# artisansTomePcb.net
KiCad netlist of a schematic drawn in EasyEDA Pro
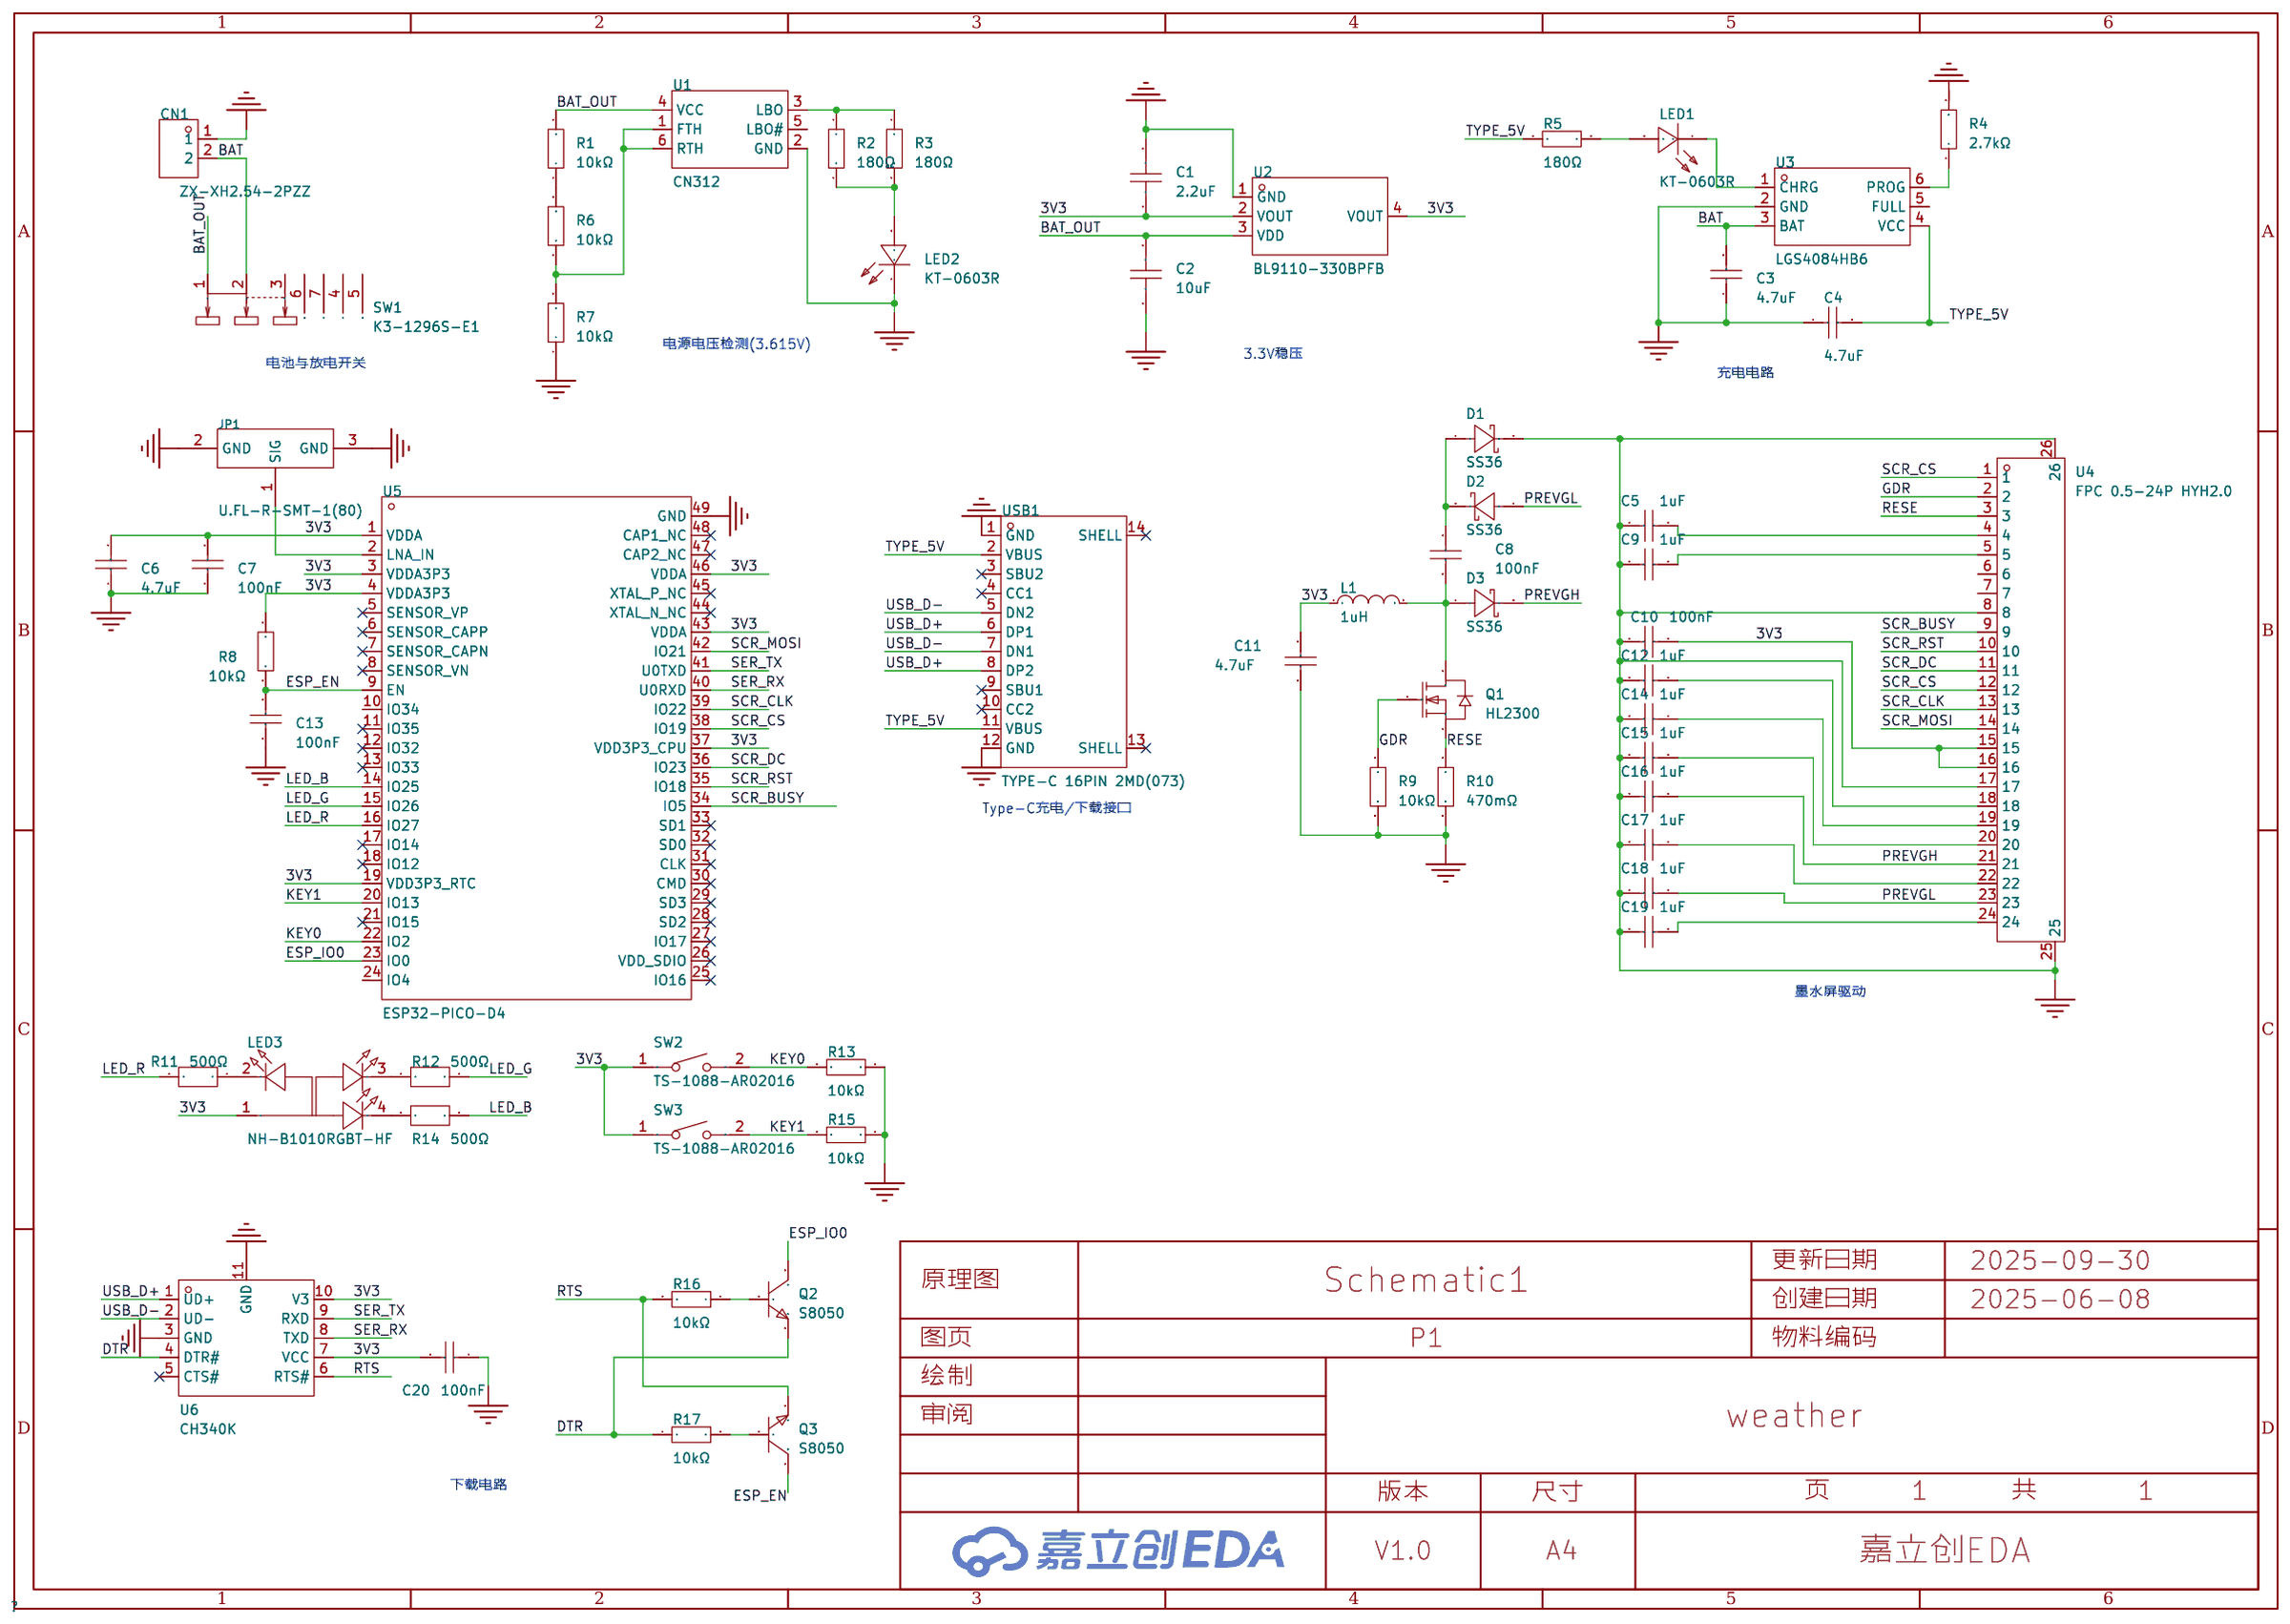
[diagram p0: schematic sheet]

(export (version "E")
  (design (tool "Eeschema 10.0.6"))
  (components
    (comp (ref "C1")
      (value "2.2uF")
      (footprint "easyedapro:C0402")
      (description "容值:2.2uF;精度:±10%;额定电压:16V;材质(温度系数):X5R;")
      (fields
        (field (name "Manufacturer Part") "HGC0402R5225K160NTEJ")
        (field (name "Manufacturer") "Chinocera(华瓷)")
      )
      (libsource (lib "easyedapro") (part "HGC0402R5225K160NTEJ"))
    )
    (comp (ref "C2")
      (value "10uF")
      (footprint "easyedapro:C0402")
      (description "容值:10uF;精度:±20%;额定电压:10V;材质(温度系数):X5R;")
      (fields
        (field (name "Manufacturer Part") "CGA0402X5R106M100GT")
        (field (name "Manufacturer") "HRE(芯声)")
      )
      (libsource (lib "easyedapro") (part "CGA0402X5R106M100GT"))
    )
    (comp (ref "C3")
      (value "4.7uF")
      (footprint "easyedapro:C0402")
      (description "容值:10uF;精度:±20%;额定电压:6.3V;材质(温度系数):X5R;")
      (fields
        (field (name "Manufacturer Part") "CL05A475MP5NRNC")
        (field (name "Manufacturer") "SAMSUNG(三星)")
      )
      (libsource (lib "easyedapro") (part "CL05A106MQ5NUNC"))
    )
    (comp (ref "C4")
      (value "4.7uF")
      (footprint "easyedapro:C0402")
      (description "容值:10uF;精度:±20%;额定电压:6.3V;材质(温度系数):X5R;")
      (fields
        (field (name "Manufacturer Part") "CL05A475MP5NRNC")
        (field (name "Manufacturer") "SAMSUNG(三星)")
      )
      (libsource (lib "easyedapro") (part "CL05A106MQ5NUNC"))
    )
    (comp (ref "C5")
      (value "1uF")
      (footprint "easyedapro:C0402")
      (description "容值:10uF;精度:±20%;额定电压:6.3V;材质(温度系数):X5R;")
      (fields
        (field (name "Manufacturer Part") "CL05A106MQ5NUNC")
        (field (name "Manufacturer") "SAMSUNG(三星)")
      )
      (libsource (lib "easyedapro") (part "CL05A106MQ5NUNC"))
    )
    (comp (ref "C6")
      (value "4.7uF")
      (footprint "easyedapro:C0402")
      (description "容值:10uF;精度:±20%;额定电压:6.3V;材质(温度系数):X5R;")
      (fields
        (field (name "Manufacturer Part") "CL05A475MP5NRNC")
        (field (name "Manufacturer") "SAMSUNG(三星)")
      )
      (libsource (lib "easyedapro") (part "CL05A106MQ5NUNC"))
    )
    (comp (ref "C7")
      (value "100nF")
      (footprint "easyedapro:C0402")
      (description "容值:100nF;精度:±10%;额定电压:16V;材质(温度系数):X7R;")
      (fields
        (field (name "Manufacturer Part") "CL05B104KO5NNNC")
        (field (name "Manufacturer") "SAMSUNG(三星)")
      )
      (libsource (lib "easyedapro") (part "CL05B104KO5NNNC"))
    )
    (comp (ref "C8")
      (value "100nF")
      (footprint "easyedapro:C0402")
      (description "容值:100nF;精度:±10%;额定电压:16V;温度系数:X7R;")
      (fields
        (field (name "Manufacturer Part") "CL05A106MQ5NUNC")
        (field (name "Manufacturer") "SAMSUNG(三星)")
      )
      (libsource (lib "easyedapro") (part "CL05A106MQ5NUNC"))
    )
    (comp (ref "C9")
      (value "1uF")
      (footprint "easyedapro:C0402")
      (description "容值:10uF;精度:±20%;额定电压:6.3V;材质(温度系数):X5R;")
      (fields
        (field (name "Manufacturer Part") "CL05A106MQ5NUNC")
        (field (name "Manufacturer") "SAMSUNG(三星)")
      )
      (libsource (lib "easyedapro") (part "CL05A106MQ5NUNC"))
    )
    (comp (ref "C10")
      (value "100nF")
      (footprint "easyedapro:C0402")
      (description "容值:100nF;精度:±10%;额定电压:16V;材质(温度系数):X7R;")
      (fields
        (field (name "Manufacturer Part") "CL05B104KO5NNNC")
        (field (name "Manufacturer") "SAMSUNG(三星)")
      )
      (libsource (lib "easyedapro") (part "CL05B104KO5NNNC"))
    )
    (comp (ref "C11")
      (value "4.7uF")
      (footprint "easyedapro:C0402")
      (description "容值:10uF;精度:±20%;额定电压:6.3V;材质(温度系数):X5R;")
      (fields
        (field (name "Manufacturer Part") "CL05A475MP5NRNC")
        (field (name "Manufacturer") "SAMSUNG(三星)")
      )
      (libsource (lib "easyedapro") (part "CL05A106MQ5NUNC"))
    )
    (comp (ref "C12")
      (value "1uF")
      (footprint "easyedapro:C0402")
      (description "容值:10uF;精度:±20%;额定电压:6.3V;材质(温度系数):X5R;")
      (fields
        (field (name "Manufacturer Part") "CL05A106MQ5NUNC")
        (field (name "Manufacturer") "SAMSUNG(三星)")
      )
      (libsource (lib "easyedapro") (part "CL05A106MQ5NUNC"))
    )
    (comp (ref "C13")
      (value "100nF")
      (footprint "easyedapro:C0402")
      (description "容值:100nF;精度:±10%;额定电压:16V;材质(温度系数):X7R;")
      (fields
        (field (name "Manufacturer Part") "CL05B104KO5NNNC")
        (field (name "Manufacturer") "SAMSUNG(三星)")
      )
      (libsource (lib "easyedapro") (part "CL05B104KO5NNNC"))
    )
    (comp (ref "C14")
      (value "1uF")
      (footprint "easyedapro:C0402")
      (description "容值:10uF;精度:±20%;额定电压:6.3V;材质(温度系数):X5R;")
      (fields
        (field (name "Manufacturer Part") "CL05A106MQ5NUNC")
        (field (name "Manufacturer") "SAMSUNG(三星)")
      )
      (libsource (lib "easyedapro") (part "CL05A106MQ5NUNC"))
    )
    (comp (ref "C15")
      (value "1uF")
      (footprint "easyedapro:C0402")
      (description "容值:10uF;精度:±20%;额定电压:6.3V;材质(温度系数):X5R;")
      (fields
        (field (name "Manufacturer Part") "CL05A106MQ5NUNC")
        (field (name "Manufacturer") "SAMSUNG(三星)")
      )
      (libsource (lib "easyedapro") (part "CL05A106MQ5NUNC"))
    )
    (comp (ref "C16")
      (value "1uF")
      (footprint "easyedapro:C0402")
      (description "容值:10uF;精度:±20%;额定电压:6.3V;材质(温度系数):X5R;")
      (fields
        (field (name "Manufacturer Part") "CL05A106MQ5NUNC")
        (field (name "Manufacturer") "SAMSUNG(三星)")
      )
      (libsource (lib "easyedapro") (part "CL05A106MQ5NUNC"))
    )
    (comp (ref "C17")
      (value "1uF")
      (footprint "easyedapro:C0402")
      (description "容值:10uF;精度:±20%;额定电压:6.3V;材质(温度系数):X5R;")
      (fields
        (field (name "Manufacturer Part") "CL05A106MQ5NUNC")
        (field (name "Manufacturer") "SAMSUNG(三星)")
      )
      (libsource (lib "easyedapro") (part "CL05A106MQ5NUNC"))
    )
    (comp (ref "C18")
      (value "1uF")
      (footprint "easyedapro:C0402")
      (description "容值:10uF;精度:±20%;额定电压:6.3V;材质(温度系数):X5R;")
      (fields
        (field (name "Manufacturer Part") "CL05A106MQ5NUNC")
        (field (name "Manufacturer") "SAMSUNG(三星)")
      )
      (libsource (lib "easyedapro") (part "CL05A106MQ5NUNC"))
    )
    (comp (ref "C19")
      (value "1uF")
      (footprint "easyedapro:C0402")
      (description "容值:10uF;精度:±20%;额定电压:6.3V;材质(温度系数):X5R;")
      (fields
        (field (name "Manufacturer Part") "CL05A106MQ5NUNC")
        (field (name "Manufacturer") "SAMSUNG(三星)")
      )
      (libsource (lib "easyedapro") (part "CL05A106MQ5NUNC"))
    )
    (comp (ref "C20")
      (value "100nF")
      (footprint "easyedapro:C0402")
      (description "容值:100nF;精度:±10%;额定电压:16V;材质(温度系数):X7R;")
      (fields
        (field (name "Manufacturer Part") "CL05B104KO5NNNC")
        (field (name "Manufacturer") "SAMSUNG(三星)")
      )
      (libsource (lib "easyedapro") (part "CL05B104KO5NNNC"))
    )
    (comp (ref "CN1")
      (value "ZX-XH2.54-2PZZ")
      (footprint "easyedapro:CONN-TH_2P-P2.50_HX25003-2A")
      (fields (field (name "Manufacturer") "Megastar(兆星)"))
      (libsource (lib "easyedapro") (part "ZX-XH2.54-2PZZ"))
    )
    (comp (ref "D1")
      (value "SS36")
      (footprint "easyedapro:SMA_L4.3-W2.6-LS5.0-FD")
      (description "二极管配置:独立式;正向压降(Vf):700mV@3.0A;直流反向耐压(Vr):60V;整流电流:3A;")
      (fields (field (name "Manufacturer") "R+O(宏嘉诚)"))
      (libsource (lib "easyedapro") (part "SS36_C7420367"))
    )
    (comp (ref "D2")
      (value "SS36")
      (footprint "easyedapro:SMA_L4.3-W2.6-LS5.0-FD")
      (description "二极管配置:独立式;正向压降(Vf):700mV@3.0A;直流反向耐压(Vr):60V;整流电流:3A;")
      (fields (field (name "Manufacturer") "R+O(宏嘉诚)"))
      (libsource (lib "easyedapro") (part "SS36_C7420367"))
    )
    (comp (ref "D3")
      (value "SS36")
      (footprint "easyedapro:SMA_L4.3-W2.6-LS5.0-FD")
      (description "二极管配置:独立式;正向压降(Vf):700mV@3.0A;直流反向耐压(Vr):60V;整流电流:3A;")
      (fields (field (name "Manufacturer") "R+O(宏嘉诚)"))
      (libsource (lib "easyedapro") (part "SS36_C7420367"))
    )
    (comp (ref "JP1")
      (value "U.FL-R-SMT-1(80)")
      (footprint "easyedapro:RF-SMD_FRF05002-JSS103M")
      (fields (field (name "Manufacturer") "HRS(广濑)"))
      (libsource (lib "easyedapro") (part "U.FL-R-SMT-1(80)"))
    )
    (comp (ref "L1")
      (value "1uH")
      (footprint "easyedapro:IND-SMD_L2.0-W1.6-B")
      (description "电感值:1uH;精度:±20%;额定电流:4.5A;饱和电流(Isat):4.6A;类型:一体成型电感;")
      (fields
        (field (name "Manufacturer Part") "FTC201610S1R0MBCA")
        (field (name "Manufacturer") "cjiang(长江微电)")
      )
      (libsource (lib "easyedapro") (part "FTC201610S1R0MBCA"))
    )
    (comp (ref "LED1")
      (value "KT-0603R")
      (footprint "easyedapro:LED0603-RD")
      (description "发光颜色:红色;功率:-;正向电流:-;主波长:-;二极管配置:-;透镜颜色:-;色温:-;发光角度:-;载带方式:-;工作温度:-40°C~+85°C;")
      (fields (field (name "Manufacturer") "KENTO"))
      (libsource (lib "easyedapro") (part "KT-0603R"))
    )
    (comp (ref "LED2")
      (value "KT-0603R")
      (footprint "easyedapro:LED0603-RD")
      (description "发光颜色:红色;功率:-;正向电流:-;主波长:-;二极管配置:-;透镜颜色:-;色温:-;发光角度:-;载带方式:-;工作温度:-40°C~+85°C;")
      (fields (field (name "Manufacturer") "KENTO"))
      (libsource (lib "easyedapro") (part "KT-0603R"))
    )
    (comp (ref "LED3")
      (value "NH-B1010RGBT-HF")
      (footprint "easyedapro:LED-ARRAY-SMD_4P-L1.0-W1.0-TR_NH-B1010RGBT")
      (description "户内RGB，全黑框架，对比度高，黑色哑光封装，无镜面反射")
      (fields (field (name "Manufacturer") "国星光电"))
      (libsource (lib "easyedapro") (part "NH-B1010RGBT-HF"))
    )
    (comp (ref "Q1")
      (value "HL2300")
      (footprint "easyedapro:SOT-23-3_L2.9-W1.3-P1.90-LS2.4-BR")
      (fields (field (name "Manufacturer") "R+O(宏嘉诚)"))
      (libsource (lib "easyedapro") (part "HL2300_C7420343"))
    )
    (comp (ref "Q2")
      (value "S8050")
      (footprint "easyedapro:SOT-23-3_L2.9-W1.6-P1.90-LS2.8-BR")
      (description "晶体管类型:NPN;集电极电流(Ic):500mA;集射极击穿电压(Vceo):25V;功率(Pd):300mW;")
      (fields (field (name "Manufacturer") "Hottech(合科泰)"))
      (libsource (lib "easyedapro") (part "S8050_C181158"))
    )
    (comp (ref "Q3")
      (value "S8050")
      (footprint "easyedapro:SOT-23-3_L2.9-W1.6-P1.90-LS2.8-BR")
      (description "晶体管类型:NPN;集电极电流(Ic):500mA;集射极击穿电压(Vceo):25V;功率(Pd):300mW;")
      (fields (field (name "Manufacturer") "Hottech(合科泰)"))
      (libsource (lib "easyedapro") (part "S8050_C181158"))
    )
    (comp (ref "R1")
      (value "10kΩ")
      (footprint "easyedapro:R0603")
      (description "电阻类型:厚膜电阻;阻值:10kΩ;精度:±1%;功率:100mW;最大工作电压:75V;温度系数:±100ppm/°C;")
      (fields
        (field (name "Manufacturer Part") "0402WGF1002TCE")
        (field (name "Manufacturer") "UNI-ROYAL(厚声)")
      )
      (libsource (lib "easyedapro") (part "0603WAF1002T5E"))
    )
    (comp (ref "R2")
      (value "180Ω")
      (fields
        (field (name "Manufacturer Part") "0402WGF1800TCE")
        (field (name "Manufacturer") "UNI-ROYAL(厚声)")
      )
      (libsource (lib "easyedapro") (part "0603WAF1800T5E"))
    )
    (comp (ref "R3")
      (value "180Ω")
      (fields
        (field (name "Manufacturer Part") "0402WGF1800TCE")
        (field (name "Manufacturer") "UNI-ROYAL(厚声)")
      )
      (libsource (lib "easyedapro") (part "0603WAF1800T5E"))
    )
    (comp (ref "R4")
      (value "2.7kΩ")
      (footprint "easyedapro:R0402")
      (description "电阻类型:厚膜电阻;阻值:2.7kΩ;精度:±1%;功率:62.5mW;最大工作电压:50V;温度系数:±100ppm/°C;")
      (fields
        (field (name "Manufacturer Part") "0402WGF2701TCE")
        (field (name "Manufacturer") "UNI-ROYAL(厚声)")
      )
      (libsource (lib "easyedapro") (part "0402WGF2701TCE"))
    )
    (comp (ref "R5")
      (value "180Ω")
      (fields
        (field (name "Manufacturer Part") "0402WGF1800TCE")
        (field (name "Manufacturer") "UNI-ROYAL(厚声)")
      )
      (libsource (lib "easyedapro") (part "0603WAF1800T5E"))
    )
    (comp (ref "R6")
      (value "10kΩ")
      (footprint "easyedapro:R0603")
      (description "电阻类型:厚膜电阻;阻值:10kΩ;精度:±1%;功率:100mW;最大工作电压:75V;温度系数:±100ppm/°C;")
      (fields
        (field (name "Manufacturer Part") "0402WGF1002TCE")
        (field (name "Manufacturer") "UNI-ROYAL(厚声)")
      )
      (libsource (lib "easyedapro") (part "0603WAF1002T5E"))
    )
    (comp (ref "R7")
      (value "10kΩ")
      (footprint "easyedapro:R0603")
      (description "电阻类型:厚膜电阻;阻值:10kΩ;精度:±1%;功率:100mW;最大工作电压:75V;温度系数:±100ppm/°C;")
      (fields
        (field (name "Manufacturer Part") "0402WGF1002TCE")
        (field (name "Manufacturer") "UNI-ROYAL(厚声)")
      )
      (libsource (lib "easyedapro") (part "0603WAF1002T5E"))
    )
    (comp (ref "R8")
      (value "10kΩ")
      (footprint "easyedapro:R0603")
      (description "电阻类型:厚膜电阻;阻值:10kΩ;精度:±1%;功率:100mW;最大工作电压:75V;温度系数:±100ppm/°C;")
      (fields
        (field (name "Manufacturer Part") "0402WGF1002TCE")
        (field (name "Manufacturer") "UNI-ROYAL(厚声)")
      )
      (libsource (lib "easyedapro") (part "0603WAF1002T5E"))
    )
    (comp (ref "R9")
      (value "10kΩ")
      (description "电阻类型:厚膜电阻;阻值:10kΩ;精度:±1%;功率:62.5mW;工作电压:50V;温度系数:±100ppm/℃;")
      (fields
        (field (name "Manufacturer Part") "0402WGF1002TCE")
        (field (name "Manufacturer") "UNI-ROYAL(厚声)")
      )
      (libsource (lib "easyedapro") (part "0603WAF1800T5E"))
    )
    (comp (ref "R10")
      (value "470mΩ")
      (fields
        (field (name "Manufacturer Part") "0402WGF470LTCE")
        (field (name "Manufacturer") "UNI-ROYAL(厚声)")
      )
      (libsource (lib "easyedapro") (part "0603WAF1800T5E"))
    )
    (comp (ref "R11")
      (value "500Ω")
      (footprint "easyedapro:R0402")
      (description "电阻类型:薄膜电阻;阻值:500Ω;精度:±1%;功率:63mW;温度系数:±50ppm/°C;")
      (fields (field (name "Manufacturer Part") "RT0402FRE07500RL") (field (name "Manufacturer") "YAGEO(国巨)"))
      (libsource (lib "easyedapro") (part "RT0402FRE07500RL"))
    )
    (comp (ref "R12")
      (value "500Ω")
      (footprint "easyedapro:R0402")
      (description "电阻类型:薄膜电阻;阻值:500Ω;精度:±1%;功率:63mW;温度系数:±50ppm/°C;")
      (fields (field (name "Manufacturer Part") "RT0402FRE07500RL") (field (name "Manufacturer") "YAGEO(国巨)"))
      (libsource (lib "easyedapro") (part "RT0402FRE07500RL"))
    )
    (comp (ref "R13")
      (value "10kΩ")
      (footprint "easyedapro:R0603")
      (description "电阻类型:厚膜电阻;阻值:10kΩ;精度:±1%;功率:100mW;最大工作电压:75V;温度系数:±100ppm/°C;")
      (fields
        (field (name "Manufacturer Part") "0402WGF1002TCE")
        (field (name "Manufacturer") "UNI-ROYAL(厚声)")
      )
      (libsource (lib "easyedapro") (part "0603WAF1002T5E"))
    )
    (comp (ref "R14")
      (value "500Ω")
      (footprint "easyedapro:R0402")
      (description "电阻类型:薄膜电阻;阻值:500Ω;精度:±1%;功率:63mW;温度系数:±50ppm/°C;")
      (fields (field (name "Manufacturer Part") "RT0402FRE07500RL") (field (name "Manufacturer") "YAGEO(国巨)"))
      (libsource (lib "easyedapro") (part "RT0402FRE07500RL"))
    )
    (comp (ref "R15")
      (value "10kΩ")
      (footprint "easyedapro:R0603")
      (description "电阻类型:厚膜电阻;阻值:10kΩ;精度:±1%;功率:100mW;最大工作电压:75V;温度系数:±100ppm/°C;")
      (fields
        (field (name "Manufacturer Part") "0402WGF1002TCE")
        (field (name "Manufacturer") "UNI-ROYAL(厚声)")
      )
      (libsource (lib "easyedapro") (part "0603WAF1002T5E"))
    )
    (comp (ref "R16")
      (value "10kΩ")
      (footprint "easyedapro:R0603")
      (description "电阻类型:厚膜电阻;阻值:10kΩ;精度:±1%;功率:100mW;最大工作电压:75V;温度系数:±100ppm/°C;")
      (fields
        (field (name "Manufacturer Part") "0402WGF1002TCE")
        (field (name "Manufacturer") "UNI-ROYAL(厚声)")
      )
      (libsource (lib "easyedapro") (part "0603WAF1002T5E"))
    )
    (comp (ref "R17")
      (value "10kΩ")
      (footprint "easyedapro:R0603")
      (description "电阻类型:厚膜电阻;阻值:10kΩ;精度:±1%;功率:100mW;最大工作电压:75V;温度系数:±100ppm/°C;")
      (fields
        (field (name "Manufacturer Part") "0402WGF1002TCE")
        (field (name "Manufacturer") "UNI-ROYAL(厚声)")
      )
      (libsource (lib "easyedapro") (part "0603WAF1002T5E"))
    )
    (comp (ref "SW1")
      (value "K3-1296S-E1")
      (footprint "easyedapro:SW-TH_K3-1296S-E1")
      (description "电路结构:单刀双掷;安装方式:卧贴;开关颜色:黑色;额定电流(DC):300mA;额定电压(DC):4V;额定电流(AC):-;额定电压(AC):-;机械寿命:1万次;")
      (fields (field (name "Manufacturer") "韩国韩荣"))
      (libsource (lib "easyedapro") (part "K3-1296S-E1_C128955"))
    )
    (comp (ref "SW2")
      (value "TS-1088-AR02016")
      (footprint "easyedapro:SW-SMD_L3.9-W3.0-P4.45")
      (fields (field (name "Manufacturer") "XUNPU(讯普)"))
      (libsource (lib "easyedapro") (part "TS-1088-AR02016"))
    )
    (comp (ref "SW3")
      (value "TS-1088-AR02016")
      (footprint "easyedapro:SW-SMD_L3.9-W3.0-P4.45")
      (fields (field (name "Manufacturer") "XUNPU(讯普)"))
      (libsource (lib "easyedapro") (part "TS-1088-AR02016"))
    )
    (comp (ref "U1")
      (value "CN312")
      (footprint "easyedapro:SOT-23-6_L2.9-W1.6-P0.95-LS2.8-BL")
      (description "集成电路")
      (fields (field (name "Manufacturer") "CONSONANCE(上海如韵)"))
      (libsource (lib "easyedapro") (part "CN312"))
    )
    (comp (ref "U2")
      (value "BL9110-330BPFB")
      (footprint "easyedapro:SOT-223_L6.5-W3.5-P2.30-LS7.0-BR")
      (description "输出类型:固定;最大输入电压:6V;输出电压:3.3V;最大输出电流:1A;电源纹波抑制比(PSRR):70dB@(1kHz);输出极性:正极;")
      (fields (field (name "Manufacturer") "BL(上海贝岭)"))
      (libsource (lib "easyedapro") (part "BL9110-330BPFB"))
    )
    (comp (ref "U3")
      (value "LGS4084HB6")
      (footprint "easyedapro:SOT-23-6_L2.9-W1.6-P0.95-LS2.8-BL")
      (description "电源电压:4V~6V;最大充电电流:500mA;电池类型:锂离子/聚合物;电池节数:1;")
      (fields (field (name "Manufacturer") "Legend-Si(棱晶半导体)"))
      (libsource (lib "easyedapro") (part "LGS4084HB6"))
    )
    (comp (ref "U4")
      (value "FPC 0.5-24P HYH2.0")
      (footprint "easyedapro:FPC-SMD_24P-P0.50_FPC-0.5-24P-HYH2.0")
      (description "锁定特性:翻盖式;触点类型:双侧触点/上下接;触点数量:24P;间距:0.5mm;安装方式:卧贴;工作温度:-25°C~+85°C;")
      (fields (field (name "Manufacturer") "SHOU HAN(首韩)"))
      (libsource (lib "easyedapro") (part "FPC 0.5-24P HYH2.0"))
    )
    (comp (ref "U5")
      (value "ESP32-PICO-D4")
      (footprint "easyedapro:LGA-48_L7.0-W7.0-P0.50-BL-EP5.4")
      (fields (field (name "Manufacturer") "ESPRESSIF(乐鑫)"))
      (libsource (lib "easyedapro") (part "ESP32-PICO-D4"))
    )
    (comp (ref "U6")
      (value "CH340K")
      (footprint "easyedapro:ESOP-10_L4.9-W3.9-P1.00-LS6.0-BL-EP")
      (fields (field (name "Manufacturer") "WCH(南京沁恒)"))
      (libsource (lib "easyedapro") (part "CH340K_C18208922"))
    )
    (comp (ref "USB1")
      (value "TYPE-C 16PIN 2MD(073)")
      (footprint "easyedapro:USB-C-SMD_TYPE-C-6PIN-2MD-073")
      (description "连接器类型:Type-C;标准:-;公母:母;端口数量:1;触点数量:16P;安装方式:卧贴;额定电流 - 电源:5A;工作温度范围:-25°C~+85°C;")
      (fields (field (name "Manufacturer") "SHOU HAN(首韩)"))
      (libsource (lib "easyedapro") (part "TYPE-C 16PIN 2MD(073)"))
    )
  )
  (nets
    (net (code "1") (name "/3V3") (class "Default")
      (node (ref "C1") (pin "1") (pinfunction "1_1") (pintype "unspecified"))
      (node (ref "C10") (pin "1") (pinfunction "1_1") (pintype "input"))
      (node (ref "C11") (pin "2") (pinfunction "2_2") (pintype "input"))
      (node (ref "C20") (pin "2") (pinfunction "2_2") (pintype "input"))
      (node (ref "C6") (pin "2") (pinfunction "2_2") (pintype "input"))
      (node (ref "C7") (pin "2") (pinfunction "2_2") (pintype "input"))
      (node (ref "L1") (pin "1") (pinfunction "1_1") (pintype "unspecified"))
      (node (ref "LED3") (pin "1") (pinfunction "+_1") (pintype "unspecified"))
      (node (ref "R8") (pin "1") (pinfunction "1_1") (pintype "input"))
      (node (ref "SW2") (pin "1") (pinfunction "1_1") (pintype "unspecified"))
      (node (ref "SW3") (pin "1") (pinfunction "1_1") (pintype "unspecified"))
      (node (ref "U2") (pin "2") (pinfunction "VOUT_2") (pintype "input"))
      (node (ref "U2") (pin "4") (pinfunction "VOUT_4") (pintype "input"))
      (node (ref "U4") (pin "15") (pinfunction "15_15") (pintype "unspecified"))
      (node (ref "U4") (pin "16") (pinfunction "16_16") (pintype "unspecified"))
      (node (ref "U5") (pin "1") (pinfunction "VDDA_1") (pintype "unspecified"))
      (node (ref "U5") (pin "19") (pinfunction "VDD3P3_RTC_19") (pintype "unspecified"))
      (node (ref "U5") (pin "3") (pinfunction "VDDA3P3_3") (pintype "unspecified"))
      (node (ref "U5") (pin "37") (pinfunction "VDD3P3_CPU_37") (pintype "unspecified"))
      (node (ref "U5") (pin "4") (pinfunction "VDDA3P3_4") (pintype "unspecified"))
      (node (ref "U5") (pin "43") (pinfunction "VDDA_43") (pintype "unspecified"))
      (node (ref "U5") (pin "46") (pinfunction "VDDA_46") (pintype "unspecified"))
      (node (ref "U6") (pin "10") (pinfunction "V3_10") (pintype "unspecified"))
      (node (ref "U6") (pin "7") (pinfunction "VCC_7") (pintype "unspecified"))
    )
    (net (code "2") (name "/BAT") (class "Default")
      (node (ref "C3") (pin "2") (pinfunction "2_2") (pintype "input"))
      (node (ref "CN1") (pin "2") (pinfunction "2_2") (pintype "unspecified"))
      (node (ref "SW1") (pin "2") (pinfunction "2_2") (pintype "unspecified"))
      (node (ref "U3") (pin "3") (pinfunction "BAT_3") (pintype "unspecified"))
    )
    (net (code "3") (name "/BAT_OUT") (class "Default")
      (node (ref "C2") (pin "2") (pinfunction "2_2") (pintype "unspecified"))
      (node (ref "R1") (pin "2") (pinfunction "2_2") (pintype "input"))
      (node (ref "SW1") (pin "1") (pinfunction "1_1") (pintype "unspecified"))
      (node (ref "U1") (pin "4") (pinfunction "VCC_4") (pintype "unspecified"))
      (node (ref "U2") (pin "3") (pinfunction "VDD_3") (pintype "input"))
    )
    (net (code "4") (name "/DTR") (class "Default")
      (node (ref "Q2") (pin "2") (pinfunction "2_2") (pintype "input"))
      (node (ref "R17") (pin "1") (pinfunction "1_1") (pintype "input"))
      (node (ref "U6") (pin "4") (pinfunction "DTR#_4") (pintype "unspecified"))
    )
    (net (code "5") (name "/ESP_EN") (class "Default")
      (node (ref "C13") (pin "2") (pinfunction "2_2") (pintype "input"))
      (node (ref "Q3") (pin "3") (pinfunction "3_3") (pintype "input"))
      (node (ref "R8") (pin "2") (pinfunction "2_2") (pintype "input"))
      (node (ref "U5") (pin "9") (pinfunction "EN_9") (pintype "unspecified"))
    )
    (net (code "6") (name "/ESP_IO0") (class "Default")
      (node (ref "Q2") (pin "3") (pinfunction "3_3") (pintype "input"))
      (node (ref "U5") (pin "23") (pinfunction "IO0_23") (pintype "unspecified"))
    )
    (net (code "7") (name "/GDR") (class "Default")
      (node (ref "Q1") (pin "1") (pinfunction "G_1") (pintype "unspecified"))
      (node (ref "R9") (pin "1") (pinfunction "1_1") (pintype "input"))
      (node (ref "U4") (pin "2") (pinfunction "2_2") (pintype "unspecified"))
    )
    (net (code "8") (name "/KEY0") (class "Default")
      (node (ref "R13") (pin "2") (pinfunction "2_2") (pintype "input"))
      (node (ref "SW2") (pin "2") (pinfunction "2_2") (pintype "unspecified"))
      (node (ref "U5") (pin "22") (pinfunction "IO2_22") (pintype "unspecified"))
    )
    (net (code "9") (name "/KEY1") (class "Default")
      (node (ref "R15") (pin "2") (pinfunction "2_2") (pintype "input"))
      (node (ref "SW3") (pin "2") (pinfunction "2_2") (pintype "unspecified"))
      (node (ref "U5") (pin "20") (pinfunction "IO13_20") (pintype "unspecified"))
    )
    (net (code "10") (name "/LED_B") (class "Default")
      (node (ref "R14") (pin "1") (pinfunction "1_1") (pintype "unspecified"))
      (node (ref "U5") (pin "14") (pinfunction "IO25_14") (pintype "unspecified"))
    )
    (net (code "11") (name "/LED_G") (class "Default")
      (node (ref "R12") (pin "1") (pinfunction "1_1") (pintype "unspecified"))
      (node (ref "U5") (pin "15") (pinfunction "IO26_15") (pintype "unspecified"))
    )
    (net (code "12") (name "/LED_R") (class "Default")
      (node (ref "R11") (pin "2") (pinfunction "2_2") (pintype "unspecified"))
      (node (ref "U5") (pin "16") (pinfunction "IO27_16") (pintype "unspecified"))
    )
    (net (code "13") (name "/PREVGH") (class "Default")
      (node (ref "C16") (pin "1") (pinfunction "1_1") (pintype "input"))
      (node (ref "D3") (pin "2") (pinfunction "K_2") (pintype "unspecified"))
      (node (ref "U4") (pin "21") (pinfunction "21_21") (pintype "unspecified"))
    )
    (net (code "14") (name "/PREVGL") (class "Default")
      (node (ref "C18") (pin "1") (pinfunction "1_1") (pintype "input"))
      (node (ref "D2") (pin "1") (pinfunction "A_1") (pintype "unspecified"))
      (node (ref "U4") (pin "23") (pinfunction "23_23") (pintype "unspecified"))
    )
    (net (code "15") (name "/RESE") (class "Default")
      (node (ref "Q1") (pin "2") (pinfunction "S_2") (pintype "unspecified"))
      (node (ref "R10") (pin "1") (pinfunction "1_1") (pintype "input"))
      (node (ref "U4") (pin "3") (pinfunction "3_3") (pintype "unspecified"))
    )
    (net (code "16") (name "/RTS") (class "Default")
      (node (ref "Q3") (pin "2") (pinfunction "2_2") (pintype "input"))
      (node (ref "R16") (pin "2") (pinfunction "2_2") (pintype "input"))
      (node (ref "U6") (pin "6") (pinfunction "RTS#_6") (pintype "unspecified"))
    )
    (net (code "17") (name "/SCR_BUSY") (class "Default")
      (node (ref "U4") (pin "9") (pinfunction "9_9") (pintype "unspecified"))
      (node (ref "U5") (pin "34") (pinfunction "IO5_34") (pintype "unspecified"))
    )
    (net (code "18") (name "/SCR_CLK") (class "Default")
      (node (ref "U4") (pin "13") (pinfunction "13_13") (pintype "unspecified"))
      (node (ref "U5") (pin "39") (pinfunction "IO22_39") (pintype "unspecified"))
    )
    (net (code "19") (name "/SCR_CS") (class "Default")
      (node (ref "U4") (pin "1") (pinfunction "1_1") (pintype "unspecified"))
      (node (ref "U4") (pin "12") (pinfunction "12_12") (pintype "unspecified"))
      (node (ref "U5") (pin "38") (pinfunction "IO19_38") (pintype "unspecified"))
    )
    (net (code "20") (name "/SCR_DC") (class "Default")
      (node (ref "U4") (pin "11") (pinfunction "11_11") (pintype "unspecified"))
      (node (ref "U5") (pin "36") (pinfunction "IO23_36") (pintype "unspecified"))
    )
    (net (code "21") (name "/SCR_MOSI") (class "Default")
      (node (ref "U4") (pin "14") (pinfunction "14_14") (pintype "unspecified"))
      (node (ref "U5") (pin "42") (pinfunction "IO21_42") (pintype "unspecified"))
    )
    (net (code "22") (name "/SCR_RST") (class "Default")
      (node (ref "U4") (pin "10") (pinfunction "10_10") (pintype "unspecified"))
      (node (ref "U5") (pin "35") (pinfunction "IO18_35") (pintype "unspecified"))
    )
    (net (code "23") (name "/SER_RX") (class "Default")
      (node (ref "U5") (pin "40") (pinfunction "U0RXD_40") (pintype "unspecified"))
      (node (ref "U6") (pin "8") (pinfunction "TXD_8") (pintype "unspecified"))
    )
    (net (code "24") (name "/SER_TX") (class "Default")
      (node (ref "U5") (pin "41") (pinfunction "U0TXD_41") (pintype "unspecified"))
      (node (ref "U6") (pin "9") (pinfunction "RXD_9") (pintype "unspecified"))
    )
    (net (code "25") (name "/TYPE_5V") (class "Default")
      (node (ref "C4") (pin "2") (pinfunction "2_2") (pintype "input"))
      (node (ref "R5") (pin "1") (pinfunction "1_1") (pintype "input"))
      (node (ref "U3") (pin "4") (pinfunction "VCC_4") (pintype "unspecified"))
      (node (ref "USB1") (pin "11") (pinfunction "VBUS_11") (pintype "unspecified"))
      (node (ref "USB1") (pin "2") (pinfunction "VBUS_2") (pintype "unspecified"))
    )
    (net (code "26") (name "/USB_D+") (class "Default")
      (node (ref "U6") (pin "1") (pinfunction "UD+_1") (pintype "unspecified"))
      (node (ref "USB1") (pin "6") (pinfunction "DP1_6") (pintype "unspecified"))
      (node (ref "USB1") (pin "8") (pinfunction "DP2_8") (pintype "unspecified"))
    )
    (net (code "27") (name "/USB_D-") (class "Default")
      (node (ref "U6") (pin "2") (pinfunction "UD-_2") (pintype "unspecified"))
      (node (ref "USB1") (pin "5") (pinfunction "DN2_5") (pintype "unspecified"))
      (node (ref "USB1") (pin "7") (pinfunction "DN1_7") (pintype "unspecified"))
    )
    (net (code "28") (name "GND") (class "Default")
      (node (ref "C1") (pin "2") (pinfunction "2_2") (pintype "unspecified"))
      (node (ref "C10") (pin "2") (pinfunction "2_2") (pintype "input"))
      (node (ref "C11") (pin "1") (pinfunction "1_1") (pintype "input"))
      (node (ref "C12") (pin "2") (pinfunction "2_2") (pintype "input"))
      (node (ref "C13") (pin "1") (pinfunction "1_1") (pintype "input"))
      (node (ref "C14") (pin "2") (pinfunction "2_2") (pintype "input"))
      (node (ref "C15") (pin "2") (pinfunction "2_2") (pintype "input"))
      (node (ref "C16") (pin "2") (pinfunction "2_2") (pintype "input"))
      (node (ref "C17") (pin "2") (pinfunction "2_2") (pintype "input"))
      (node (ref "C18") (pin "2") (pinfunction "2_2") (pintype "input"))
      (node (ref "C19") (pin "2") (pinfunction "2_2") (pintype "input"))
      (node (ref "C2") (pin "1") (pinfunction "1_1") (pintype "unspecified"))
      (node (ref "C20") (pin "1") (pinfunction "1_1") (pintype "input"))
      (node (ref "C3") (pin "1") (pinfunction "1_1") (pintype "input"))
      (node (ref "C4") (pin "1") (pinfunction "1_1") (pintype "input"))
      (node (ref "C5") (pin "2") (pinfunction "2_2") (pintype "input"))
      (node (ref "C6") (pin "1") (pinfunction "1_1") (pintype "input"))
      (node (ref "C7") (pin "1") (pinfunction "1_1") (pintype "input"))
      (node (ref "C9") (pin "2") (pinfunction "2_2") (pintype "input"))
      (node (ref "CN1") (pin "1") (pinfunction "1_1") (pintype "unspecified"))
      (node (ref "D1") (pin "2") (pinfunction "K_2") (pintype "unspecified"))
      (node (ref "JP1") (pin "2") (pinfunction "GND_2") (pintype "input"))
      (node (ref "JP1") (pin "3") (pinfunction "GND_3") (pintype "input"))
      (node (ref "LED2") (pin "1") (pinfunction "K_1") (pintype "input"))
      (node (ref "R10") (pin "2") (pinfunction "2_2") (pintype "input"))
      (node (ref "R13") (pin "1") (pinfunction "1_1") (pintype "input"))
      (node (ref "R15") (pin "1") (pinfunction "1_1") (pintype "input"))
      (node (ref "R4") (pin "2") (pinfunction "2_2") (pintype "input"))
      (node (ref "R7") (pin "1") (pinfunction "1_1") (pintype "input"))
      (node (ref "R9") (pin "2") (pinfunction "2_2") (pintype "input"))
      (node (ref "U1") (pin "2") (pinfunction "GND_2") (pintype "unspecified"))
      (node (ref "U2") (pin "1") (pinfunction "GND_1") (pintype "input"))
      (node (ref "U3") (pin "2") (pinfunction "GND_2") (pintype "unspecified"))
      (node (ref "U4") (pin "17") (pinfunction "17_17") (pintype "unspecified"))
      (node (ref "U4") (pin "25") (pinfunction "25_25") (pintype "unspecified"))
      (node (ref "U4") (pin "26") (pinfunction "26_26") (pintype "unspecified"))
      (node (ref "U4") (pin "8") (pinfunction "8_8") (pintype "unspecified"))
      (node (ref "U5") (pin "49") (pinfunction "GND_49") (pintype "unspecified"))
      (node (ref "U6") (pin "11") (pinfunction "GND_11") (pintype "unspecified"))
      (node (ref "U6") (pin "3") (pinfunction "GND_3") (pintype "unspecified"))
      (node (ref "USB1") (pin "1") (pinfunction "GND_1") (pintype "unspecified"))
      (node (ref "USB1") (pin "12") (pinfunction "GND_12") (pintype "unspecified"))
    )
    (net (code "29") (name "Net-(C5-Pad1)") (class "Default")
      (node (ref "C5") (pin "1") (pinfunction "1_1") (pintype "input"))
      (node (ref "U4") (pin "4") (pinfunction "4_4") (pintype "unspecified"))
    )
    (net (code "30") (name "Net-(C9-Pad1)") (class "Default")
      (node (ref "C9") (pin "1") (pinfunction "1_1") (pintype "input"))
      (node (ref "U4") (pin "5") (pinfunction "5_5") (pintype "unspecified"))
    )
    (net (code "31") (name "Net-(C12-Pad1)") (class "Default")
      (node (ref "C12") (pin "1") (pinfunction "1_1") (pintype "input"))
      (node (ref "U4") (pin "18") (pinfunction "18_18") (pintype "unspecified"))
    )
    (net (code "32") (name "Net-(C14-Pad1)") (class "Default")
      (node (ref "C14") (pin "1") (pinfunction "1_1") (pintype "input"))
      (node (ref "U4") (pin "19") (pinfunction "19_19") (pintype "unspecified"))
    )
    (net (code "33") (name "Net-(C15-Pad1)") (class "Default")
      (node (ref "C15") (pin "1") (pinfunction "1_1") (pintype "input"))
      (node (ref "U4") (pin "20") (pinfunction "20_20") (pintype "unspecified"))
    )
    (net (code "34") (name "Net-(C17-Pad1)") (class "Default")
      (node (ref "C17") (pin "1") (pinfunction "1_1") (pintype "input"))
      (node (ref "U4") (pin "22") (pinfunction "22_22") (pintype "unspecified"))
    )
    (net (code "35") (name "Net-(C19-Pad1)") (class "Default")
      (node (ref "C19") (pin "1") (pinfunction "1_1") (pintype "input"))
      (node (ref "U4") (pin "24") (pinfunction "24_24") (pintype "unspecified"))
    )
    (net (code "36") (name "Net-(D1-A)") (class "Default")
      (node (ref "C8") (pin "2") (pinfunction "2_2") (pintype "input"))
      (node (ref "D1") (pin "1") (pinfunction "A_1") (pintype "unspecified"))
      (node (ref "D2") (pin "2") (pinfunction "K_2") (pintype "unspecified"))
    )
    (net (code "37") (name "Net-(D3-A)") (class "Default")
      (node (ref "C8") (pin "1") (pinfunction "1_1") (pintype "input"))
      (node (ref "D3") (pin "1") (pinfunction "A_1") (pintype "unspecified"))
      (node (ref "L1") (pin "2") (pinfunction "2_2") (pintype "unspecified"))
      (node (ref "Q1") (pin "3") (pinfunction "D_3") (pintype "unspecified"))
    )
    (net (code "38") (name "Net-(JP1-SIG)") (class "Default")
      (node (ref "JP1") (pin "1") (pinfunction "SIG_1") (pintype "input"))
      (node (ref "U5") (pin "2") (pinfunction "LNA_IN_2") (pintype "unspecified"))
    )
    (net (code "39") (name "Net-(LED1-A)") (class "Default")
      (node (ref "LED1") (pin "2") (pinfunction "A_2") (pintype "input"))
      (node (ref "R5") (pin "2") (pinfunction "2_2") (pintype "input"))
    )
    (net (code "40") (name "Net-(LED1-K)") (class "Default")
      (node (ref "LED1") (pin "1") (pinfunction "K_1") (pintype "input"))
      (node (ref "U3") (pin "1") (pinfunction "CHRG_1") (pintype "unspecified"))
    )
    (net (code "41") (name "Net-(LED2-A)") (class "Default")
      (node (ref "LED2") (pin "2") (pinfunction "A_2") (pintype "input"))
      (node (ref "R2") (pin "2") (pinfunction "2_2") (pintype "input"))
      (node (ref "R3") (pin "2") (pinfunction "2_2") (pintype "input"))
    )
    (net (code "42") (name "Net-(LED3---Pad2)") (class "Default")
      (node (ref "LED3") (pin "2") (pinfunction "-_2") (pintype "unspecified"))
      (node (ref "R11") (pin "1") (pinfunction "1_1") (pintype "unspecified"))
    )
    (net (code "43") (name "Net-(LED3---Pad3)") (class "Default")
      (node (ref "LED3") (pin "3") (pinfunction "-_3") (pintype "unspecified"))
      (node (ref "R12") (pin "2") (pinfunction "2_2") (pintype "unspecified"))
    )
    (net (code "44") (name "Net-(LED3---Pad4)") (class "Default")
      (node (ref "LED3") (pin "4") (pinfunction "-_4") (pintype "unspecified"))
      (node (ref "R14") (pin "2") (pinfunction "2_2") (pintype "unspecified"))
    )
    (net (code "45") (name "Net-(Q2-Pad1)") (class "Default")
      (node (ref "Q2") (pin "1") (pinfunction "1_1") (pintype "input"))
      (node (ref "R16") (pin "1") (pinfunction "1_1") (pintype "input"))
    )
    (net (code "46") (name "Net-(Q3-Pad1)") (class "Default")
      (node (ref "Q3") (pin "1") (pinfunction "1_1") (pintype "input"))
      (node (ref "R17") (pin "2") (pinfunction "2_2") (pintype "input"))
    )
    (net (code "47") (name "Net-(R1-Pad1)") (class "Default")
      (node (ref "R1") (pin "1") (pinfunction "1_1") (pintype "input"))
      (node (ref "R6") (pin "2") (pinfunction "2_2") (pintype "input"))
    )
    (net (code "48") (name "Net-(U1-FTH)") (class "Default")
      (node (ref "R6") (pin "1") (pinfunction "1_1") (pintype "input"))
      (node (ref "R7") (pin "2") (pinfunction "2_2") (pintype "input"))
      (node (ref "U1") (pin "1") (pinfunction "FTH_1") (pintype "unspecified"))
      (node (ref "U1") (pin "6") (pinfunction "RTH_6") (pintype "unspecified"))
    )
    (net (code "49") (name "Net-(U1-LBO)") (class "Default")
      (node (ref "R2") (pin "1") (pinfunction "1_1") (pintype "input"))
      (node (ref "R3") (pin "1") (pinfunction "1_1") (pintype "input"))
      (node (ref "U1") (pin "3") (pinfunction "LBO_3") (pintype "unspecified"))
    )
    (net (code "50") (name "Net-(U3-PROG)") (class "Default")
      (node (ref "R4") (pin "1") (pinfunction "1_1") (pintype "input"))
      (node (ref "U3") (pin "6") (pinfunction "PROG_6") (pintype "unspecified"))
    )
    (net (code "51") (name "unconnected-(SW1-Pad3)") (class "Default")
      (node (ref "SW1") (pin "3") (pinfunction "3_3") (pintype "unspecified"))
    )
    (net (code "52") (name "unconnected-(SW1-Pad4)") (class "Default")
      (node (ref "SW1") (pin "4") (pinfunction "4_4") (pintype "unspecified"))
    )
    (net (code "53") (name "unconnected-(SW1-Pad5)") (class "Default")
      (node (ref "SW1") (pin "5") (pinfunction "5_5") (pintype "unspecified"))
    )
    (net (code "54") (name "unconnected-(SW1-Pad6)") (class "Default")
      (node (ref "SW1") (pin "6") (pinfunction "6_6") (pintype "unspecified"))
    )
    (net (code "55") (name "unconnected-(SW1-Pad7)") (class "Default")
      (node (ref "SW1") (pin "7") (pinfunction "7_7") (pintype "unspecified"))
    )
    (net (code "56") (name "unconnected-(U1-LBO#-Pad5)") (class "Default")
      (node (ref "U1") (pin "5") (pinfunction "LBO#_5") (pintype "unspecified"))
    )
    (net (code "57") (name "unconnected-(U3-FULL-Pad5)") (class "Default")
      (node (ref "U3") (pin "5") (pinfunction "FULL_5") (pintype "unspecified"))
    )
    (net (code "58") (name "unconnected-(U4-Pad6)") (class "Default")
      (node (ref "U4") (pin "6") (pinfunction "6_6") (pintype "unspecified"))
    )
    (net (code "59") (name "unconnected-(U4-Pad7)") (class "Default")
      (node (ref "U4") (pin "7") (pinfunction "7_7") (pintype "unspecified"))
    )
    (net (code "60") (name "unconnected-(U5-CAP1_NC-Pad48)") (class "Default")
      (node (ref "U5") (pin "48") (pinfunction "CAP1_NC_48") (pintype "unspecified+no_connect"))
    )
    (net (code "61") (name "unconnected-(U5-CAP2_NC-Pad47)") (class "Default")
      (node (ref "U5") (pin "47") (pinfunction "CAP2_NC_47") (pintype "unspecified+no_connect"))
    )
    (net (code "62") (name "unconnected-(U5-CLK-Pad31)") (class "Default")
      (node (ref "U5") (pin "31") (pinfunction "CLK_31") (pintype "unspecified+no_connect"))
    )
    (net (code "63") (name "unconnected-(U5-CMD-Pad30)") (class "Default")
      (node (ref "U5") (pin "30") (pinfunction "CMD_30") (pintype "unspecified+no_connect"))
    )
    (net (code "64") (name "unconnected-(U5-IO4-Pad24)") (class "Default")
      (node (ref "U5") (pin "24") (pinfunction "IO4_24") (pintype "unspecified"))
    )
    (net (code "65") (name "unconnected-(U5-IO12-Pad18)") (class "Default")
      (node (ref "U5") (pin "18") (pinfunction "IO12_18") (pintype "unspecified+no_connect"))
    )
    (net (code "66") (name "unconnected-(U5-IO14-Pad17)") (class "Default")
      (node (ref "U5") (pin "17") (pinfunction "IO14_17") (pintype "unspecified+no_connect"))
    )
    (net (code "67") (name "unconnected-(U5-IO15-Pad21)") (class "Default")
      (node (ref "U5") (pin "21") (pinfunction "IO15_21") (pintype "unspecified+no_connect"))
    )
    (net (code "68") (name "unconnected-(U5-IO16-Pad25)") (class "Default")
      (node (ref "U5") (pin "25") (pinfunction "IO16_25") (pintype "unspecified+no_connect"))
    )
    (net (code "69") (name "unconnected-(U5-IO17-Pad27)") (class "Default")
      (node (ref "U5") (pin "27") (pinfunction "IO17_27") (pintype "unspecified+no_connect"))
    )
    (net (code "70") (name "unconnected-(U5-IO32-Pad12)") (class "Default")
      (node (ref "U5") (pin "12") (pinfunction "IO32_12") (pintype "unspecified+no_connect"))
    )
    (net (code "71") (name "unconnected-(U5-IO33-Pad13)") (class "Default")
      (node (ref "U5") (pin "13") (pinfunction "IO33_13") (pintype "unspecified+no_connect"))
    )
    (net (code "72") (name "unconnected-(U5-IO34-Pad10)") (class "Default")
      (node (ref "U5") (pin "10") (pinfunction "IO34_10") (pintype "unspecified"))
    )
    (net (code "73") (name "unconnected-(U5-IO35-Pad11)") (class "Default")
      (node (ref "U5") (pin "11") (pinfunction "IO35_11") (pintype "unspecified+no_connect"))
    )
    (net (code "74") (name "unconnected-(U5-SD0-Pad32)") (class "Default")
      (node (ref "U5") (pin "32") (pinfunction "SD0_32") (pintype "unspecified+no_connect"))
    )
    (net (code "75") (name "unconnected-(U5-SD1-Pad33)") (class "Default")
      (node (ref "U5") (pin "33") (pinfunction "SD1_33") (pintype "unspecified+no_connect"))
    )
    (net (code "76") (name "unconnected-(U5-SD2-Pad28)") (class "Default")
      (node (ref "U5") (pin "28") (pinfunction "SD2_28") (pintype "unspecified+no_connect"))
    )
    (net (code "77") (name "unconnected-(U5-SD3-Pad29)") (class "Default")
      (node (ref "U5") (pin "29") (pinfunction "SD3_29") (pintype "unspecified+no_connect"))
    )
    (net (code "78") (name "unconnected-(U5-SENSOR_CAPN-Pad7)") (class "Default")
      (node (ref "U5") (pin "7") (pinfunction "SENSOR_CAPN_7") (pintype "unspecified+no_connect"))
    )
    (net (code "79") (name "unconnected-(U5-SENSOR_CAPP-Pad6)") (class "Default")
      (node (ref "U5") (pin "6") (pinfunction "SENSOR_CAPP_6") (pintype "unspecified+no_connect"))
    )
    (net (code "80") (name "unconnected-(U5-SENSOR_VN-Pad8)") (class "Default")
      (node (ref "U5") (pin "8") (pinfunction "SENSOR_VN_8") (pintype "unspecified+no_connect"))
    )
    (net (code "81") (name "unconnected-(U5-SENSOR_VP-Pad5)") (class "Default")
      (node (ref "U5") (pin "5") (pinfunction "SENSOR_VP_5") (pintype "unspecified+no_connect"))
    )
    (net (code "82") (name "unconnected-(U5-VDD_SDIO-Pad26)") (class "Default")
      (node (ref "U5") (pin "26") (pinfunction "VDD_SDIO_26") (pintype "unspecified+no_connect"))
    )
    (net (code "83") (name "unconnected-(U5-XTAL_N_NC-Pad44)") (class "Default")
      (node (ref "U5") (pin "44") (pinfunction "XTAL_N_NC_44") (pintype "unspecified+no_connect"))
    )
    (net (code "84") (name "unconnected-(U5-XTAL_P_NC-Pad45)") (class "Default")
      (node (ref "U5") (pin "45") (pinfunction "XTAL_P_NC_45") (pintype "unspecified+no_connect"))
    )
    (net (code "85") (name "unconnected-(U6-CTS#-Pad5)") (class "Default")
      (node (ref "U6") (pin "5") (pinfunction "CTS#_5") (pintype "unspecified+no_connect"))
    )
    (net (code "86") (name "unconnected-(USB1-CC1-Pad4)") (class "Default")
      (node (ref "USB1") (pin "4") (pinfunction "CC1_4") (pintype "unspecified+no_connect"))
    )
    (net (code "87") (name "unconnected-(USB1-CC2-Pad10)") (class "Default")
      (node (ref "USB1") (pin "10") (pinfunction "CC2_10") (pintype "unspecified+no_connect"))
    )
    (net (code "88") (name "unconnected-(USB1-SBU1-Pad9)") (class "Default")
      (node (ref "USB1") (pin "9") (pinfunction "SBU1_9") (pintype "unspecified+no_connect"))
    )
    (net (code "89") (name "unconnected-(USB1-SBU2-Pad3)") (class "Default")
      (node (ref "USB1") (pin "3") (pinfunction "SBU2_3") (pintype "unspecified+no_connect"))
    )
    (net (code "90") (name "unconnected-(USB1-SHELL-Pad13)") (class "Default")
      (node (ref "USB1") (pin "13") (pinfunction "SHELL_13") (pintype "unspecified+no_connect"))
    )
    (net (code "91") (name "unconnected-(USB1-SHELL-Pad14)") (class "Default")
      (node (ref "USB1") (pin "14") (pinfunction "SHELL_14") (pintype "unspecified+no_connect"))
    )
  )
)
